# MCUboard.net
KiCad netlist of a schematic drawn in Altium Designer
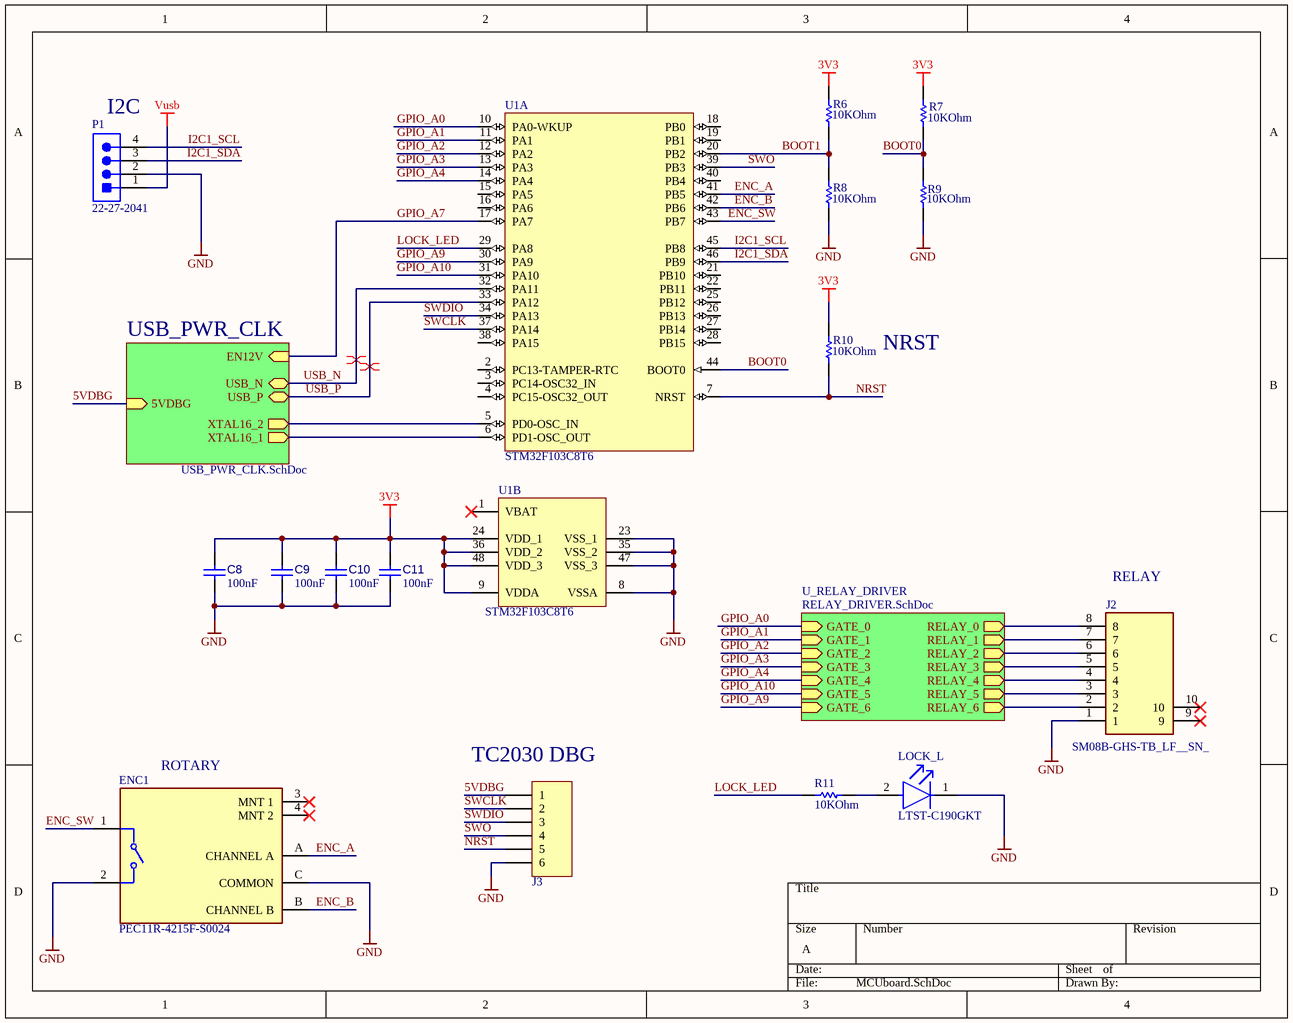
[diagram p0: MCUboard.SchDoc]

(export (version "E")
  (design (tool "Eeschema 10.0.6"))
  (components
    (comp (ref "C8")
      (value "100nF")
      (footprint "CAPC1608X90X40NL10T20")
      (description "Chip Capacitor, 100 nF, +/- 10%, 50 V, 0603 (1608 Metric)")
      (fields (field (name "TOLERANCE") "10%") (field (name "Comment") "Capacitor 100 nF +/-10% 50 V 0603"))
      (libsource (lib "Nebraska Instruments") (part "CAP-NP-2"))
    )
    (comp (ref "C9")
      (value "100nF")
      (footprint "CAPC1608X90X40NL10T20")
      (description "Chip Capacitor, 100 nF, +/- 10%, 50 V, 0603 (1608 Metric)")
      (fields (field (name "TOLERANCE") "10%") (field (name "Comment") "Capacitor 100 nF +/-10% 50 V 0603"))
      (libsource (lib "Nebraska Instruments") (part "CAP-NP-2"))
    )
    (comp (ref "C10")
      (value "100nF")
      (footprint "CAPC1608X90X40NL10T20")
      (description "Chip Capacitor, 100 nF, +/- 10%, 50 V, 0603 (1608 Metric)")
      (fields (field (name "TOLERANCE") "10%") (field (name "Comment") "Capacitor 100 nF +/-10% 50 V 0603"))
      (libsource (lib "Nebraska Instruments") (part "CAP-NP-2"))
    )
    (comp (ref "C11")
      (value "100nF")
      (footprint "CAPC1608X90X40NL10T20")
      (description "Chip Capacitor, 100 nF, +/- 10%, 50 V, 0603 (1608 Metric)")
      (fields (field (name "TOLERANCE") "10%") (field (name "Comment") "Capacitor 100 nF +/-10% 50 V 0603"))
      (libsource (lib "Nebraska Instruments") (part "CAP-NP-2"))
    )
    (comp (ref "ENC1")
      (value "PEC11R-4215F-S0024")
      (footprint "FP-PEC11R-4215F-S0024-MFG")
      (description "ROTARY ENCODER MECHANICAL 24PPR")
      (libsource (lib "Altium Content Vault") (part "5f1dd25a4c49fa66e7eeb899730fe11"))
    )
    (comp (ref "J2")
      (value "SM08B-GHS-TB_LF__SN_")
      (footprint "SamacSys:SM08BGHSTBLFSN")
      (description "Connector")
      (fields (field (name "MANUFACTURER_PART_NUMBER") "SM08B-GHS-TB(LF)(SN)"))
      (libsource (lib "*") (part "SM08B-GHS-TB_LF__SN_"))
    )
    (comp (ref "J3")
      (value "ICSP")
      (footprint "TC2030-MCP-NL")
      (libsource (lib "Nebraska Instruments") (part "ICSP"))
    )
    (comp (ref "LOCK_L")
      (value "LTST-C190GKT")
      (footprint "FP-LTST-C190GKT-MFG")
      (description "LED GREEN CLEAR CHIP SMD")
      (fields (field (name "VOLTAGE") "2V"))
      (libsource (lib "Altium Content Vault") (part "8706943c75ba83719d021d2fdc84c58"))
    )
    (comp (ref "P1")
      (value "22-27-2041")
      (footprint "MOLX-22-27-2041_V")
      (description "Male Header, Pitch 2.54 mm, 1 x 4 Position, Height 11.7 mm, Tail Length 3.56 mm, RoHS, Bulk")
      (fields (field (name "MANUFACTURER") "Molex"))
      (libsource (lib "Altium Content Vault") (part "CN-1P-M-R4"))
    )
    (comp (ref "R6")
      (value "ERJ3EKF1002V")
      (footprint "RESC1609X55X30LL15T15")
      (description "Chip Resistor, 10 KOhm, +/- 1%, 0.1 W, -55 to 155 degC, 0603 (1608 Metric), RoHS, Tape and Reel")
      (fields
        (field (name "RESISTANCE") "10KOhm")
        (field (name "TOLERANCE") "1%")
        (field (name "MANUFACTURER") "Panasonic")
      )
      (libsource (lib "Altium Content Vault") (part "RES-2"))
    )
    (comp (ref "R7")
      (value "ERJ3EKF1002V")
      (footprint "RESC1609X55X30LL15T15")
      (description "Chip Resistor, 10 KOhm, +/- 1%, 0.1 W, -55 to 155 degC, 0603 (1608 Metric), RoHS, Tape and Reel")
      (fields
        (field (name "RESISTANCE") "10KOhm")
        (field (name "TOLERANCE") "1%")
        (field (name "MANUFACTURER") "Panasonic")
      )
      (libsource (lib "Altium Content Vault") (part "RES-2"))
    )
    (comp (ref "R8")
      (value "ERJ3EKF1002V")
      (footprint "RESC1609X55X30LL15T15")
      (description "Chip Resistor, 10 KOhm, +/- 1%, 0.1 W, -55 to 155 degC, 0603 (1608 Metric), RoHS, Tape and Reel")
      (fields
        (field (name "RESISTANCE") "10KOhm")
        (field (name "TOLERANCE") "1%")
        (field (name "MANUFACTURER") "Panasonic")
      )
      (libsource (lib "Altium Content Vault") (part "RES-2"))
    )
    (comp (ref "R9")
      (value "ERJ3EKF1002V")
      (footprint "RESC1609X55X30LL15T15")
      (description "Chip Resistor, 10 KOhm, +/- 1%, 0.1 W, -55 to 155 degC, 0603 (1608 Metric), RoHS, Tape and Reel")
      (fields
        (field (name "RESISTANCE") "10KOhm")
        (field (name "TOLERANCE") "1%")
        (field (name "MANUFACTURER") "Panasonic")
      )
      (libsource (lib "Altium Content Vault") (part "RES-2"))
    )
    (comp (ref "R10")
      (value "ERJ3EKF1002V")
      (footprint "RESC1609X55X30LL15T15")
      (description "Chip Resistor, 10 KOhm, +/- 1%, 0.1 W, -55 to 155 degC, 0603 (1608 Metric), RoHS, Tape and Reel")
      (fields
        (field (name "RESISTANCE") "10KOhm")
        (field (name "TOLERANCE") "1%")
        (field (name "MANUFACTURER") "Panasonic")
      )
      (libsource (lib "Altium Content Vault") (part "RES-2"))
    )
    (comp (ref "R11")
      (value "ERJ3EKF1002V")
      (footprint "RESC1609X55X30LL15T15")
      (description "Chip Resistor, 10 KOhm, +/- 1%, 0.1 W, -55 to 155 degC, 0603 (1608 Metric), RoHS, Tape and Reel")
      (fields
        (field (name "RESISTANCE") "10KOhm")
        (field (name "TOLERANCE") "1%")
        (field (name "MANUFACTURER") "Panasonic")
      )
      (libsource (lib "Altium Content Vault") (part "RES-2"))
    )
    (comp (ref "U1")
      (value "STM32F103C8T6")
      (footprint "STM-LQFP48_L")
      (libsource (lib "Altium Content Vault") (part "MC-ARM-STM32F103X8_B-SQ48"))
    )
  )
  (nets
    (net (code "1") (name "/5VDBG") (class "Default")
      (node (ref "J3") (pin "1") (pinfunction "1_1") (pintype "passive"))
    )
    (net (code "2") (name "/BOOT0") (class "Default")
      (node (ref "R7") (pin "1") (pinfunction "1_1") (pintype "passive"))
      (node (ref "R9") (pin "2") (pinfunction "2_2") (pintype "passive"))
      (node (ref "U1") (pin "44") (pinfunction "BOOT0_44") (pintype "input"))
    )
    (net (code "3") (name "/BOOT1") (class "Default")
      (node (ref "R6") (pin "1") (pinfunction "1_1") (pintype "passive"))
      (node (ref "R8") (pin "2") (pinfunction "2_2") (pintype "passive"))
      (node (ref "U1") (pin "20") (pinfunction "PB2_20") (pintype "bidirectional"))
    )
    (net (code "4") (name "/ENC_A") (class "Default")
      (node (ref "ENC1") (pin "A") (pinfunction "CHANNEL_A_A") (pintype "passive"))
      (node (ref "U1") (pin "41") (pinfunction "PB5_41") (pintype "bidirectional"))
    )
    (net (code "5") (name "/ENC_B") (class "Default")
      (node (ref "ENC1") (pin "B") (pinfunction "CHANNEL_B_B") (pintype "passive"))
      (node (ref "U1") (pin "42") (pinfunction "PB6_42") (pintype "bidirectional"))
    )
    (net (code "6") (name "/ENC_SW") (class "Default")
      (node (ref "ENC1") (pin "1") (pinfunction "1_1") (pintype "passive"))
      (node (ref "U1") (pin "43") (pinfunction "PB7_43") (pintype "bidirectional"))
    )
    (net (code "7") (name "/GPIO_A0") (class "Default")
      (node (ref "U1") (pin "10") (pinfunction "PA0-WKUP_10") (pintype "bidirectional"))
    )
    (net (code "8") (name "/GPIO_A1") (class "Default")
      (node (ref "U1") (pin "11") (pinfunction "PA1_11") (pintype "bidirectional"))
    )
    (net (code "9") (name "/GPIO_A2") (class "Default")
      (node (ref "U1") (pin "12") (pinfunction "PA2_12") (pintype "bidirectional"))
    )
    (net (code "10") (name "/GPIO_A3") (class "Default")
      (node (ref "U1") (pin "13") (pinfunction "PA3_13") (pintype "bidirectional"))
    )
    (net (code "11") (name "/GPIO_A4") (class "Default")
      (node (ref "U1") (pin "14") (pinfunction "PA4_14") (pintype "bidirectional"))
    )
    (net (code "12") (name "/GPIO_A7") (class "Default")
      (node (ref "U1") (pin "17") (pinfunction "PA7_17") (pintype "bidirectional"))
    )
    (net (code "13") (name "/GPIO_A9") (class "Default")
      (node (ref "U1") (pin "30") (pinfunction "PA9_30") (pintype "bidirectional"))
    )
    (net (code "14") (name "/GPIO_A10") (class "Default")
      (node (ref "U1") (pin "31") (pinfunction "PA10_31") (pintype "bidirectional"))
    )
    (net (code "15") (name "/I2C1_SCL") (class "Default")
      (node (ref "P1") (pin "4") (pinfunction "4_4") (pintype "passive"))
      (node (ref "U1") (pin "45") (pinfunction "PB8_45") (pintype "bidirectional"))
    )
    (net (code "16") (name "/I2C1_SDA") (class "Default")
      (node (ref "P1") (pin "3") (pinfunction "3_3") (pintype "passive"))
      (node (ref "U1") (pin "46") (pinfunction "PB9_46") (pintype "bidirectional"))
    )
    (net (code "17") (name "/LOCK_LED") (class "Default")
      (node (ref "R11") (pin "2") (pinfunction "2_2") (pintype "passive"))
      (node (ref "U1") (pin "29") (pinfunction "PA8_29") (pintype "bidirectional"))
    )
    (net (code "18") (name "/NRST") (class "Default")
      (node (ref "J3") (pin "5") (pinfunction "5_5") (pintype "passive"))
      (node (ref "R10") (pin "1") (pinfunction "1_1") (pintype "passive"))
      (node (ref "U1") (pin "7") (pinfunction "NRST_7") (pintype "bidirectional"))
    )
    (net (code "19") (name "/RELAY_0") (class "Default")
      (node (ref "J2") (pin "8") (pinfunction "8_8") (pintype "passive"))
    )
    (net (code "20") (name "/RELAY_1") (class "Default")
      (node (ref "J2") (pin "7") (pinfunction "7_7") (pintype "passive"))
    )
    (net (code "21") (name "/RELAY_2") (class "Default")
      (node (ref "J2") (pin "6") (pinfunction "6_6") (pintype "passive"))
    )
    (net (code "22") (name "/RELAY_3") (class "Default")
      (node (ref "J2") (pin "5") (pinfunction "5_5") (pintype "passive"))
    )
    (net (code "23") (name "/RELAY_4") (class "Default")
      (node (ref "J2") (pin "4") (pinfunction "4_4") (pintype "passive"))
    )
    (net (code "24") (name "/RELAY_5") (class "Default")
      (node (ref "J2") (pin "3") (pinfunction "3_3") (pintype "passive"))
    )
    (net (code "25") (name "/RELAY_6") (class "Default")
      (node (ref "J2") (pin "2") (pinfunction "2_2") (pintype "passive"))
    )
    (net (code "26") (name "/SWCLK") (class "Default")
      (node (ref "J3") (pin "2") (pinfunction "2_2") (pintype "passive"))
      (node (ref "U1") (pin "37") (pinfunction "PA14_37") (pintype "bidirectional"))
    )
    (net (code "27") (name "/SWDIO") (class "Default")
      (node (ref "J3") (pin "3") (pinfunction "3_3") (pintype "passive"))
      (node (ref "U1") (pin "34") (pinfunction "PA13_34") (pintype "bidirectional"))
    )
    (net (code "28") (name "/SWO") (class "Default")
      (node (ref "J3") (pin "4") (pinfunction "4_4") (pintype "passive"))
      (node (ref "U1") (pin "39") (pinfunction "PB3_39") (pintype "bidirectional"))
    )
    (net (code "29") (name "/USB_N") (class "Default")
      (node (ref "U1") (pin "32") (pinfunction "PA11_32") (pintype "bidirectional"))
    )
    (net (code "30") (name "/USB_P") (class "Default")
      (node (ref "U1") (pin "33") (pinfunction "PA12_33") (pintype "bidirectional"))
    )
    (net (code "31") (name "/XTAL16_1") (class "Default")
      (node (ref "U1") (pin "6") (pinfunction "PD1-OSC_OUT_6") (pintype "bidirectional"))
    )
    (net (code "32") (name "/XTAL16_2") (class "Default")
      (node (ref "U1") (pin "5") (pinfunction "PD0-OSC_IN_5") (pintype "bidirectional"))
    )
    (net (code "33") (name "3V3") (class "Default")
      (node (ref "C10") (pin "1") (pinfunction "1_1") (pintype "passive"))
      (node (ref "C11") (pin "1") (pinfunction "1_1") (pintype "passive"))
      (node (ref "C8") (pin "1") (pinfunction "1_1") (pintype "passive"))
      (node (ref "C9") (pin "1") (pinfunction "1_1") (pintype "passive"))
      (node (ref "R10") (pin "2") (pinfunction "2_2") (pintype "passive"))
      (node (ref "R6") (pin "2") (pinfunction "2_2") (pintype "passive"))
      (node (ref "R7") (pin "2") (pinfunction "2_2") (pintype "passive"))
      (node (ref "U1") (pin "24") (pinfunction "VDD_1_24") (pintype "power_in"))
      (node (ref "U1") (pin "36") (pinfunction "VDD_2_36") (pintype "power_in"))
      (node (ref "U1") (pin "48") (pinfunction "VDD_3_48") (pintype "power_in"))
      (node (ref "U1") (pin "9") (pinfunction "VDDA_9") (pintype "power_in"))
    )
    (net (code "34") (name "GND") (class "Default")
      (node (ref "C10") (pin "2") (pinfunction "2_2") (pintype "passive"))
      (node (ref "C11") (pin "2") (pinfunction "2_2") (pintype "passive"))
      (node (ref "C8") (pin "2") (pinfunction "2_2") (pintype "passive"))
      (node (ref "C9") (pin "2") (pinfunction "2_2") (pintype "passive"))
      (node (ref "ENC1") (pin "2") (pinfunction "2_2") (pintype "passive"))
      (node (ref "ENC1") (pin "C") (pinfunction "COMMON_C") (pintype "passive"))
      (node (ref "J2") (pin "1") (pinfunction "1_1") (pintype "passive"))
      (node (ref "J3") (pin "6") (pinfunction "6_6") (pintype "passive"))
      (node (ref "LOCK_L") (pin "1") (pinfunction "C_1") (pintype "passive"))
      (node (ref "P1") (pin "2") (pinfunction "2_2") (pintype "passive"))
      (node (ref "R8") (pin "1") (pinfunction "1_1") (pintype "passive"))
      (node (ref "R9") (pin "1") (pinfunction "1_1") (pintype "passive"))
      (node (ref "U1") (pin "23") (pinfunction "VSS_1_23") (pintype "power_in"))
      (node (ref "U1") (pin "35") (pinfunction "VSS_2_35") (pintype "power_in"))
      (node (ref "U1") (pin "47") (pinfunction "VSS_3_47") (pintype "power_in"))
      (node (ref "U1") (pin "8") (pinfunction "VSSA_8") (pintype "power_in"))
    )
    (net (code "35") (name "Net-(LOCK_L-A)") (class "Default")
      (node (ref "LOCK_L") (pin "2") (pinfunction "A_2") (pintype "passive"))
      (node (ref "R11") (pin "1") (pinfunction "1_1") (pintype "passive"))
    )
    (net (code "36") (name "Vusb") (class "Default")
      (node (ref "P1") (pin "1") (pinfunction "1_1") (pintype "passive"))
    )
    (net (code "37") (name "unconnected-(ENC1-MNT_1-Pad3)") (class "Default")
      (node (ref "ENC1") (pin "3") (pinfunction "MNT_1_3") (pintype "passive+no_connect"))
    )
    (net (code "38") (name "unconnected-(ENC1-MNT_2-Pad4)") (class "Default")
      (node (ref "ENC1") (pin "4") (pinfunction "MNT_2_4") (pintype "passive+no_connect"))
    )
    (net (code "39") (name "unconnected-(J2-Pad9)") (class "Default")
      (node (ref "J2") (pin "9") (pinfunction "9_9") (pintype "passive+no_connect"))
    )
    (net (code "40") (name "unconnected-(J2-Pad10)") (class "Default")
      (node (ref "J2") (pin "10") (pinfunction "10_10") (pintype "passive+no_connect"))
    )
    (net (code "41") (name "unconnected-(U1A-PA5-Pad15)") (class "Default")
      (node (ref "U1") (pin "15") (pinfunction "PA5_15") (pintype "bidirectional"))
    )
    (net (code "42") (name "unconnected-(U1A-PA6-Pad16)") (class "Default")
      (node (ref "U1") (pin "16") (pinfunction "PA6_16") (pintype "bidirectional"))
    )
    (net (code "43") (name "unconnected-(U1A-PA15-Pad38)") (class "Default")
      (node (ref "U1") (pin "38") (pinfunction "PA15_38") (pintype "bidirectional"))
    )
    (net (code "44") (name "unconnected-(U1A-PB0-Pad18)") (class "Default")
      (node (ref "U1") (pin "18") (pinfunction "PB0_18") (pintype "bidirectional"))
    )
    (net (code "45") (name "unconnected-(U1A-PB1-Pad19)") (class "Default")
      (node (ref "U1") (pin "19") (pinfunction "PB1_19") (pintype "bidirectional"))
    )
    (net (code "46") (name "unconnected-(U1A-PB4-Pad40)") (class "Default")
      (node (ref "U1") (pin "40") (pinfunction "PB4_40") (pintype "bidirectional"))
    )
    (net (code "47") (name "unconnected-(U1A-PB10-Pad21)") (class "Default")
      (node (ref "U1") (pin "21") (pinfunction "PB10_21") (pintype "bidirectional"))
    )
    (net (code "48") (name "unconnected-(U1A-PB11-Pad22)") (class "Default")
      (node (ref "U1") (pin "22") (pinfunction "PB11_22") (pintype "bidirectional"))
    )
    (net (code "49") (name "unconnected-(U1A-PB12-Pad25)") (class "Default")
      (node (ref "U1") (pin "25") (pinfunction "PB12_25") (pintype "bidirectional"))
    )
    (net (code "50") (name "unconnected-(U1A-PB13-Pad26)") (class "Default")
      (node (ref "U1") (pin "26") (pinfunction "PB13_26") (pintype "bidirectional"))
    )
    (net (code "51") (name "unconnected-(U1A-PB14-Pad27)") (class "Default")
      (node (ref "U1") (pin "27") (pinfunction "PB14_27") (pintype "bidirectional"))
    )
    (net (code "52") (name "unconnected-(U1A-PB15-Pad28)") (class "Default")
      (node (ref "U1") (pin "28") (pinfunction "PB15_28") (pintype "bidirectional"))
    )
    (net (code "53") (name "unconnected-(U1A-PC13-TAMPER-RTC-Pad2)") (class "Default")
      (node (ref "U1") (pin "2") (pinfunction "PC13-TAMPER-RTC_2") (pintype "bidirectional"))
    )
    (net (code "54") (name "unconnected-(U1A-PC14-OSC32_IN-Pad3)") (class "Default")
      (node (ref "U1") (pin "3") (pinfunction "PC14-OSC32_IN_3") (pintype "bidirectional"))
    )
    (net (code "55") (name "unconnected-(U1A-PC15-OSC32_OUT-Pad4)") (class "Default")
      (node (ref "U1") (pin "4") (pinfunction "PC15-OSC32_OUT_4") (pintype "bidirectional"))
    )
    (net (code "56") (name "unconnected-(U1B-VBAT-Pad1)") (class "Default")
      (node (ref "U1") (pin "1") (pinfunction "VBAT_1") (pintype "power_in+no_connect"))
    )
  )
)
